# truelog.net
KiCad netlist of a schematic drawn in EAGLE
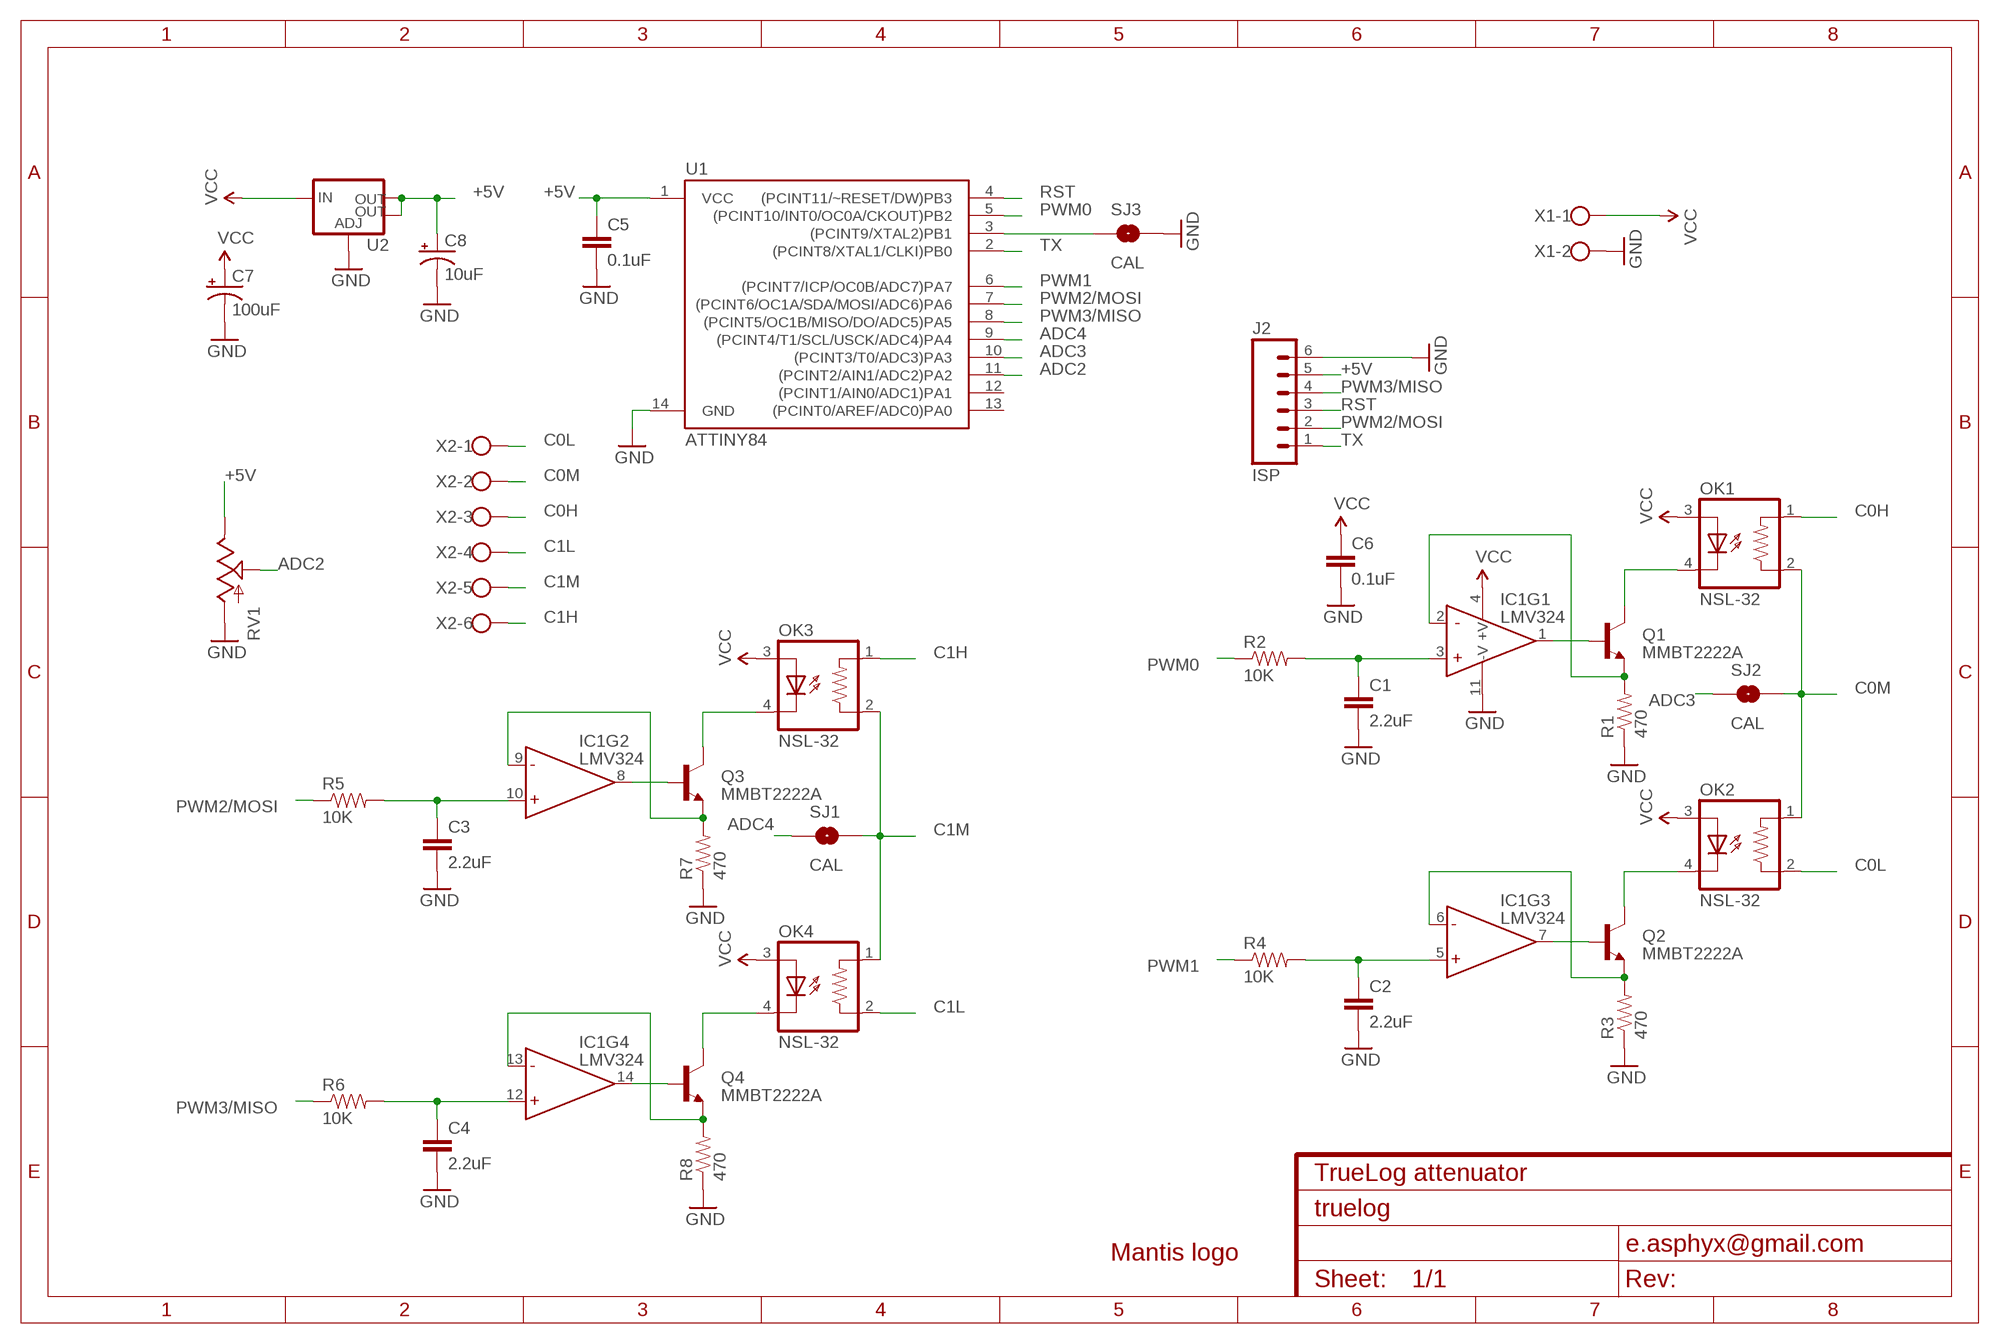
[diagram p0: schematic, sheet 1]

(export (version "E")
  (design (tool "Eeschema 10.0.6"))
  (components
    (comp (ref "C1")
      (value "2.2uF")
      (footprint "eagle-import:0805-CAP")
      (libsource (lib "eagle-import") (part "2.2UF-25V-+80/-20(0805)"))
    )
    (comp (ref "C2")
      (value "2.2uF")
      (footprint "eagle-import:0805-CAP")
      (libsource (lib "eagle-import") (part "2.2UF-25V-+80/-20(0805)"))
    )
    (comp (ref "C3")
      (value "2.2uF")
      (footprint "eagle-import:0805-CAP")
      (libsource (lib "eagle-import") (part "2.2UF-25V-+80/-20(0805)"))
    )
    (comp (ref "C4")
      (value "2.2uF")
      (footprint "eagle-import:0805-CAP")
      (libsource (lib "eagle-import") (part "2.2UF-25V-+80/-20(0805)"))
    )
    (comp (ref "C5")
      (value "0.1uF")
      (footprint "eagle-import:0603-CAP")
      (libsource (lib "eagle-import") (part "0.1UF-25V(+80/-20%)(0603)"))
    )
    (comp (ref "C6")
      (value "0.1uF")
      (footprint "eagle-import:0603-CAP")
      (libsource (lib "eagle-import") (part "0.1UF-25V(+80/-20%)(0603)"))
    )
    (comp (ref "C7")
      (value "100uF")
      (footprint "eagle-import:PANASONIC_D")
      (libsource (lib "eagle-import") (part "CAP_POLD"))
    )
    (comp (ref "C8")
      (value "10uF")
      (footprint "eagle-import:PANASONIC_C")
      (libsource (lib "eagle-import") (part "CAP_POLC"))
    )
    (comp (ref "IC1")
      (value "LMV324")
      (footprint "eagle-import:SO014")
      (libsource (lib "eagle-import") (part "LMV324"))
    )
    (comp (ref "J2")
      (value "ISP")
      (footprint "eagle-import:1X06_LOCK")
      (libsource (lib "eagle-import") (part "M06LOCK"))
    )
    (comp (ref "LOGO1")
      (value "LOGO-MANTIS")
      (footprint "eagle-import:LOGO-MANTIS")
      (libsource (lib "eagle-import") (part "LOGO-MANTIS"))
    )
    (comp (ref "OK1")
      (value "NSL-32")
      (footprint "eagle-import:NSL-OK")
      (libsource (lib "eagle-import") (part "NSL-32"))
    )
    (comp (ref "OK2")
      (value "NSL-32")
      (footprint "eagle-import:NSL-OK")
      (libsource (lib "eagle-import") (part "NSL-32"))
    )
    (comp (ref "OK3")
      (value "NSL-32")
      (footprint "eagle-import:NSL-OK")
      (libsource (lib "eagle-import") (part "NSL-32"))
    )
    (comp (ref "OK4")
      (value "NSL-32")
      (footprint "eagle-import:NSL-OK")
      (libsource (lib "eagle-import") (part "NSL-32"))
    )
    (comp (ref "Q1")
      (value "MMBT2222A")
      (footprint "eagle-import:SOT23-3")
      (libsource (lib "eagle-import") (part "TRANSISTOR_NPNMMBT2222A"))
    )
    (comp (ref "Q2")
      (value "MMBT2222A")
      (footprint "eagle-import:SOT23-3")
      (libsource (lib "eagle-import") (part "TRANSISTOR_NPNMMBT2222A"))
    )
    (comp (ref "Q3")
      (value "MMBT2222A")
      (footprint "eagle-import:SOT23-3")
      (libsource (lib "eagle-import") (part "TRANSISTOR_NPNMMBT2222A"))
    )
    (comp (ref "Q4")
      (value "MMBT2222A")
      (footprint "eagle-import:SOT23-3")
      (libsource (lib "eagle-import") (part "TRANSISTOR_NPNMMBT2222A"))
    )
    (comp (ref "R1")
      (value "470")
      (footprint "eagle-import:0805")
      (libsource (lib "eagle-import") (part "0.22OHM-1/4W-1%(0805)"))
    )
    (comp (ref "R2")
      (value "10K")
      (footprint "eagle-import:0603-RES")
      (libsource (lib "eagle-import") (part "10KOHM-1/10W-1%(0603)0603"))
    )
    (comp (ref "R3")
      (value "470")
      (footprint "eagle-import:0805")
      (libsource (lib "eagle-import") (part "0.22OHM-1/4W-1%(0805)"))
    )
    (comp (ref "R4")
      (value "10K")
      (footprint "eagle-import:0603-RES")
      (libsource (lib "eagle-import") (part "10KOHM-1/10W-1%(0603)0603"))
    )
    (comp (ref "R5")
      (value "10K")
      (footprint "eagle-import:0603-RES")
      (libsource (lib "eagle-import") (part "10KOHM-1/10W-1%(0603)0603"))
    )
    (comp (ref "R6")
      (value "10K")
      (footprint "eagle-import:0603-RES")
      (libsource (lib "eagle-import") (part "10KOHM-1/10W-1%(0603)0603"))
    )
    (comp (ref "R7")
      (value "470")
      (footprint "eagle-import:0805")
      (libsource (lib "eagle-import") (part "0.22OHM-1/4W-1%(0805)"))
    )
    (comp (ref "R8")
      (value "470")
      (footprint "eagle-import:0805")
      (libsource (lib "eagle-import") (part "0.22OHM-1/4W-1%(0805)"))
    )
    (comp (ref "RV1")
      (value "POT")
      (footprint "eagle-import:ALPS_POT")
      (libsource (lib "eagle-import") (part "POT"))
    )
    (comp (ref "SJ1")
      (value "CAL")
      (footprint "eagle-import:SJ_2S-NO")
      (libsource (lib "eagle-import") (part "SOLDERJUMPERNO"))
    )
    (comp (ref "SJ2")
      (value "CAL")
      (footprint "eagle-import:SJ_2S-NO")
      (libsource (lib "eagle-import") (part "SOLDERJUMPERNO"))
    )
    (comp (ref "SJ3")
      (value "CAL")
      (footprint "eagle-import:SJ_2S-NO")
      (libsource (lib "eagle-import") (part "SOLDERJUMPERNO"))
    )
    (comp (ref "U1")
      (value "ATTINY84")
      (footprint "eagle-import:SO14")
      (libsource (lib "eagle-import") (part "ATTINY84"))
    )
    (comp (ref "U2")
      (value "V_REG_LM1117SOT223")
      (footprint "eagle-import:SOT223")
      (libsource (lib "eagle-import") (part "V_REG_LM1117SOT223"))
    )
    (comp (ref "X1")
      (value "W237-102")
      (footprint "eagle-import:W237-102")
      (fields (field (name "MPN") "237-102"))
      (libsource (lib "eagle-import") (part "W237-102"))
    )
    (comp (ref "X2")
      (value "W237-136")
      (footprint "eagle-import:W237-136")
      (fields (field (name "MPN") "237-136"))
      (libsource (lib "eagle-import") (part "W237-136"))
    )
  )
  (nets
    (net (code "1") (name "/+5V") (class "Default")
      (node (ref "C5") (pin "1") (pinfunction "1_1") (pintype "passive"))
      (node (ref "C8") (pin "+") (pinfunction "+_+") (pintype "passive"))
      (node (ref "J2") (pin "5") (pinfunction "5_5") (pintype "passive"))
      (node (ref "RV1") (pin "P$1") (pinfunction "E_P$1") (pintype "passive"))
      (node (ref "U1") (pin "1") (pinfunction "VCC_1") (pintype "bidirectional"))
      (node (ref "U2") (pin "2") (pinfunction "OUT_2") (pintype "output"))
      (node (ref "U2") (pin "4") (pinfunction "OUT_4") (pintype "output"))
    )
    (net (code "2") (name "/ADC2") (class "Default")
      (node (ref "RV1") (pin "P$2") (pinfunction "S_P$2") (pintype "passive"))
      (node (ref "U1") (pin "11") (pinfunction "(PCINT2/AIN1/ADC2)PA2_11") (pintype "bidirectional"))
    )
    (net (code "3") (name "/ADC3") (class "Default")
      (node (ref "SJ2") (pin "1") (pinfunction "1_1") (pintype "passive"))
      (node (ref "U1") (pin "10") (pinfunction "(PCINT3/T0/ADC3)PA3_10") (pintype "bidirectional"))
    )
    (net (code "4") (name "/ADC4") (class "Default")
      (node (ref "SJ1") (pin "1") (pinfunction "1_1") (pintype "passive"))
      (node (ref "U1") (pin "9") (pinfunction "(PCINT4/T1/SCL/USCK/ADC4)PA4_9") (pintype "bidirectional"))
    )
    (net (code "5") (name "/C0H") (class "Default")
      (node (ref "OK1") (pin "1") (pinfunction "R0_1") (pintype "passive"))
      (node (ref "X2") (pin "3") (pinfunction "KL_3") (pintype "passive"))
    )
    (net (code "6") (name "/C0L") (class "Default")
      (node (ref "OK2") (pin "2") (pinfunction "R1_2") (pintype "passive"))
      (node (ref "X2") (pin "1") (pinfunction "KL_1") (pintype "passive"))
    )
    (net (code "7") (name "/C0M") (class "Default")
      (node (ref "OK1") (pin "2") (pinfunction "R1_2") (pintype "passive"))
      (node (ref "OK2") (pin "1") (pinfunction "R0_1") (pintype "passive"))
      (node (ref "SJ2") (pin "2") (pinfunction "2_2") (pintype "passive"))
      (node (ref "X2") (pin "2") (pinfunction "KL_2") (pintype "passive"))
    )
    (net (code "8") (name "/C1H") (class "Default")
      (node (ref "OK3") (pin "1") (pinfunction "R0_1") (pintype "passive"))
      (node (ref "X2") (pin "6") (pinfunction "KL_6") (pintype "passive"))
    )
    (net (code "9") (name "/C1L") (class "Default")
      (node (ref "OK4") (pin "2") (pinfunction "R1_2") (pintype "passive"))
      (node (ref "X2") (pin "4") (pinfunction "KL_4") (pintype "passive"))
    )
    (net (code "10") (name "/C1M") (class "Default")
      (node (ref "OK3") (pin "2") (pinfunction "R1_2") (pintype "passive"))
      (node (ref "OK4") (pin "1") (pinfunction "R0_1") (pintype "passive"))
      (node (ref "SJ1") (pin "2") (pinfunction "2_2") (pintype "passive"))
      (node (ref "X2") (pin "5") (pinfunction "KL_5") (pintype "passive"))
    )
    (net (code "11") (name "/PWM0") (class "Default")
      (node (ref "R2") (pin "1") (pinfunction "1_1") (pintype "passive"))
      (node (ref "U1") (pin "5") (pinfunction "(PCINT10/INT0/OC0A/CKOUT)PB2_5") (pintype "bidirectional"))
    )
    (net (code "12") (name "/PWM1") (class "Default")
      (node (ref "R4") (pin "1") (pinfunction "1_1") (pintype "passive"))
      (node (ref "U1") (pin "6") (pinfunction "(PCINT7/ICP/OC0B/ADC7)PA7_6") (pintype "bidirectional"))
    )
    (net (code "13") (name "/PWM2{slash}MOSI") (class "Default")
      (node (ref "J2") (pin "2") (pinfunction "2_2") (pintype "passive"))
      (node (ref "R5") (pin "1") (pinfunction "1_1") (pintype "passive"))
      (node (ref "U1") (pin "7") (pinfunction "(PCINT6/OC1A/SDA/MOSI/ADC6)PA6_7") (pintype "bidirectional"))
    )
    (net (code "14") (name "/PWM3{slash}MISO") (class "Default")
      (node (ref "J2") (pin "4") (pinfunction "4_4") (pintype "passive"))
      (node (ref "R6") (pin "1") (pinfunction "1_1") (pintype "passive"))
      (node (ref "U1") (pin "8") (pinfunction "(PCINT5/OC1B/MISO/DO/ADC5)PA5_8") (pintype "bidirectional"))
    )
    (net (code "15") (name "/RST") (class "Default")
      (node (ref "J2") (pin "3") (pinfunction "3_3") (pintype "passive"))
      (node (ref "U1") (pin "4") (pinfunction "(PCINT11/~{RESET/DW})PB3_4") (pintype "bidirectional"))
    )
    (net (code "16") (name "/TX") (class "Default")
      (node (ref "J2") (pin "1") (pinfunction "1_1") (pintype "passive"))
      (node (ref "U1") (pin "2") (pinfunction "(PCINT8/XTAL1/CLKI)PB0_2") (pintype "bidirectional"))
    )
    (net (code "17") (name "GND") (class "Default")
      (node (ref "C1") (pin "2") (pinfunction "2_2") (pintype "passive"))
      (node (ref "C2") (pin "2") (pinfunction "2_2") (pintype "passive"))
      (node (ref "C3") (pin "2") (pinfunction "2_2") (pintype "passive"))
      (node (ref "C4") (pin "2") (pinfunction "2_2") (pintype "passive"))
      (node (ref "C5") (pin "2") (pinfunction "2_2") (pintype "passive"))
      (node (ref "C6") (pin "2") (pinfunction "2_2") (pintype "passive"))
      (node (ref "C7") (pin "-") (pinfunction "-_-") (pintype "passive"))
      (node (ref "C8") (pin "-") (pinfunction "-_-") (pintype "passive"))
      (node (ref "IC1") (pin "11") (pinfunction "-V_11") (pintype "power_in"))
      (node (ref "J2") (pin "6") (pinfunction "6_6") (pintype "passive"))
      (node (ref "R1") (pin "1") (pinfunction "1_1") (pintype "passive"))
      (node (ref "R3") (pin "1") (pinfunction "1_1") (pintype "passive"))
      (node (ref "R7") (pin "1") (pinfunction "1_1") (pintype "passive"))
      (node (ref "R8") (pin "1") (pinfunction "1_1") (pintype "passive"))
      (node (ref "RV1") (pin "P$3") (pinfunction "A_P$3") (pintype "passive"))
      (node (ref "SJ3") (pin "2") (pinfunction "2_2") (pintype "passive"))
      (node (ref "U1") (pin "14") (pinfunction "GND_14") (pintype "bidirectional"))
      (node (ref "U2") (pin "1") (pinfunction "ADJ_1") (pintype "input"))
      (node (ref "X1") (pin "2") (pinfunction "KL_2") (pintype "passive"))
    )
    (net (code "18") (name "Net-(IC1A-+IN)") (class "Default")
      (node (ref "C1") (pin "1") (pinfunction "1_1") (pintype "passive"))
      (node (ref "IC1") (pin "3") (pinfunction "+IN_3") (pintype "input"))
      (node (ref "R2") (pin "2") (pinfunction "2_2") (pintype "passive"))
    )
    (net (code "19") (name "Net-(IC1A--IN)") (class "Default")
      (node (ref "IC1") (pin "2") (pinfunction "-IN_2") (pintype "input"))
      (node (ref "Q1") (pin "2") (pinfunction "E_2") (pintype "passive"))
      (node (ref "R1") (pin "2") (pinfunction "2_2") (pintype "passive"))
    )
    (net (code "20") (name "Net-(IC1A-OUT)") (class "Default")
      (node (ref "IC1") (pin "1") (pinfunction "OUT_1") (pintype "output"))
      (node (ref "Q1") (pin "1") (pinfunction "B_1") (pintype "passive"))
    )
    (net (code "21") (name "Net-(IC1B-+IN)") (class "Default")
      (node (ref "C3") (pin "1") (pinfunction "1_1") (pintype "passive"))
      (node (ref "IC1") (pin "10") (pinfunction "+IN_10") (pintype "input"))
      (node (ref "R5") (pin "2") (pinfunction "2_2") (pintype "passive"))
    )
    (net (code "22") (name "Net-(IC1B--IN)") (class "Default")
      (node (ref "IC1") (pin "9") (pinfunction "-IN_9") (pintype "input"))
      (node (ref "Q3") (pin "2") (pinfunction "E_2") (pintype "passive"))
      (node (ref "R7") (pin "2") (pinfunction "2_2") (pintype "passive"))
    )
    (net (code "23") (name "Net-(IC1B-OUT)") (class "Default")
      (node (ref "IC1") (pin "8") (pinfunction "OUT_8") (pintype "output"))
      (node (ref "Q3") (pin "1") (pinfunction "B_1") (pintype "passive"))
    )
    (net (code "24") (name "Net-(IC1C-+IN)") (class "Default")
      (node (ref "C2") (pin "1") (pinfunction "1_1") (pintype "passive"))
      (node (ref "IC1") (pin "5") (pinfunction "+IN_5") (pintype "input"))
      (node (ref "R4") (pin "2") (pinfunction "2_2") (pintype "passive"))
    )
    (net (code "25") (name "Net-(IC1C--IN)") (class "Default")
      (node (ref "IC1") (pin "6") (pinfunction "-IN_6") (pintype "input"))
      (node (ref "Q2") (pin "2") (pinfunction "E_2") (pintype "passive"))
      (node (ref "R3") (pin "2") (pinfunction "2_2") (pintype "passive"))
    )
    (net (code "26") (name "Net-(IC1C-OUT)") (class "Default")
      (node (ref "IC1") (pin "7") (pinfunction "OUT_7") (pintype "output"))
      (node (ref "Q2") (pin "1") (pinfunction "B_1") (pintype "passive"))
    )
    (net (code "27") (name "Net-(IC1D-+IN)") (class "Default")
      (node (ref "C4") (pin "1") (pinfunction "1_1") (pintype "passive"))
      (node (ref "IC1") (pin "12") (pinfunction "+IN_12") (pintype "input"))
      (node (ref "R6") (pin "2") (pinfunction "2_2") (pintype "passive"))
    )
    (net (code "28") (name "Net-(IC1D--IN)") (class "Default")
      (node (ref "IC1") (pin "13") (pinfunction "-IN_13") (pintype "input"))
      (node (ref "Q4") (pin "2") (pinfunction "E_2") (pintype "passive"))
      (node (ref "R8") (pin "2") (pinfunction "2_2") (pintype "passive"))
    )
    (net (code "29") (name "Net-(IC1D-OUT)") (class "Default")
      (node (ref "IC1") (pin "14") (pinfunction "OUT_14") (pintype "output"))
      (node (ref "Q4") (pin "1") (pinfunction "B_1") (pintype "passive"))
    )
    (net (code "30") (name "Net-(OK1-C)") (class "Default")
      (node (ref "OK1") (pin "4") (pinfunction "C_4") (pintype "passive"))
      (node (ref "Q1") (pin "3") (pinfunction "C_3") (pintype "passive"))
    )
    (net (code "31") (name "Net-(OK2-C)") (class "Default")
      (node (ref "OK2") (pin "4") (pinfunction "C_4") (pintype "passive"))
      (node (ref "Q2") (pin "3") (pinfunction "C_3") (pintype "passive"))
    )
    (net (code "32") (name "Net-(OK3-C)") (class "Default")
      (node (ref "OK3") (pin "4") (pinfunction "C_4") (pintype "passive"))
      (node (ref "Q3") (pin "3") (pinfunction "C_3") (pintype "passive"))
    )
    (net (code "33") (name "Net-(OK4-C)") (class "Default")
      (node (ref "OK4") (pin "4") (pinfunction "C_4") (pintype "passive"))
      (node (ref "Q4") (pin "3") (pinfunction "C_3") (pintype "passive"))
    )
    (net (code "34") (name "Net-(U1-(PCINT9{slash}XTAL2)PB1)") (class "Default")
      (node (ref "SJ3") (pin "1") (pinfunction "1_1") (pintype "passive"))
      (node (ref "U1") (pin "3") (pinfunction "(PCINT9/XTAL2)PB1_3") (pintype "bidirectional"))
    )
    (net (code "35") (name "VCC") (class "Default")
      (node (ref "C6") (pin "1") (pinfunction "1_1") (pintype "passive"))
      (node (ref "C7") (pin "+") (pinfunction "+_+") (pintype "passive"))
      (node (ref "IC1") (pin "4") (pinfunction "+V_4") (pintype "power_in"))
      (node (ref "OK1") (pin "3") (pinfunction "A_3") (pintype "passive"))
      (node (ref "OK2") (pin "3") (pinfunction "A_3") (pintype "passive"))
      (node (ref "OK3") (pin "3") (pinfunction "A_3") (pintype "passive"))
      (node (ref "OK4") (pin "3") (pinfunction "A_3") (pintype "passive"))
      (node (ref "U2") (pin "3") (pinfunction "IN_3") (pintype "input"))
      (node (ref "X1") (pin "1") (pinfunction "KL_1") (pintype "passive"))
    )
    (net (code "36") (name "unconnected-(U1-(PCINT0{slash}AREF{slash}ADC0)PA0-Pad13)") (class "Default")
      (node (ref "U1") (pin "13") (pinfunction "(PCINT0/AREF/ADC0)PA0_13") (pintype "bidirectional"))
    )
    (net (code "37") (name "unconnected-(U1-(PCINT1{slash}AIN0{slash}ADC1)PA1-Pad12)") (class "Default")
      (node (ref "U1") (pin "12") (pinfunction "(PCINT1/AIN0/ADC1)PA1_12") (pintype "bidirectional"))
    )
  )
)
